# S01-INTERFACES.net
KiCad netlist of a schematic drawn in Altium Designer
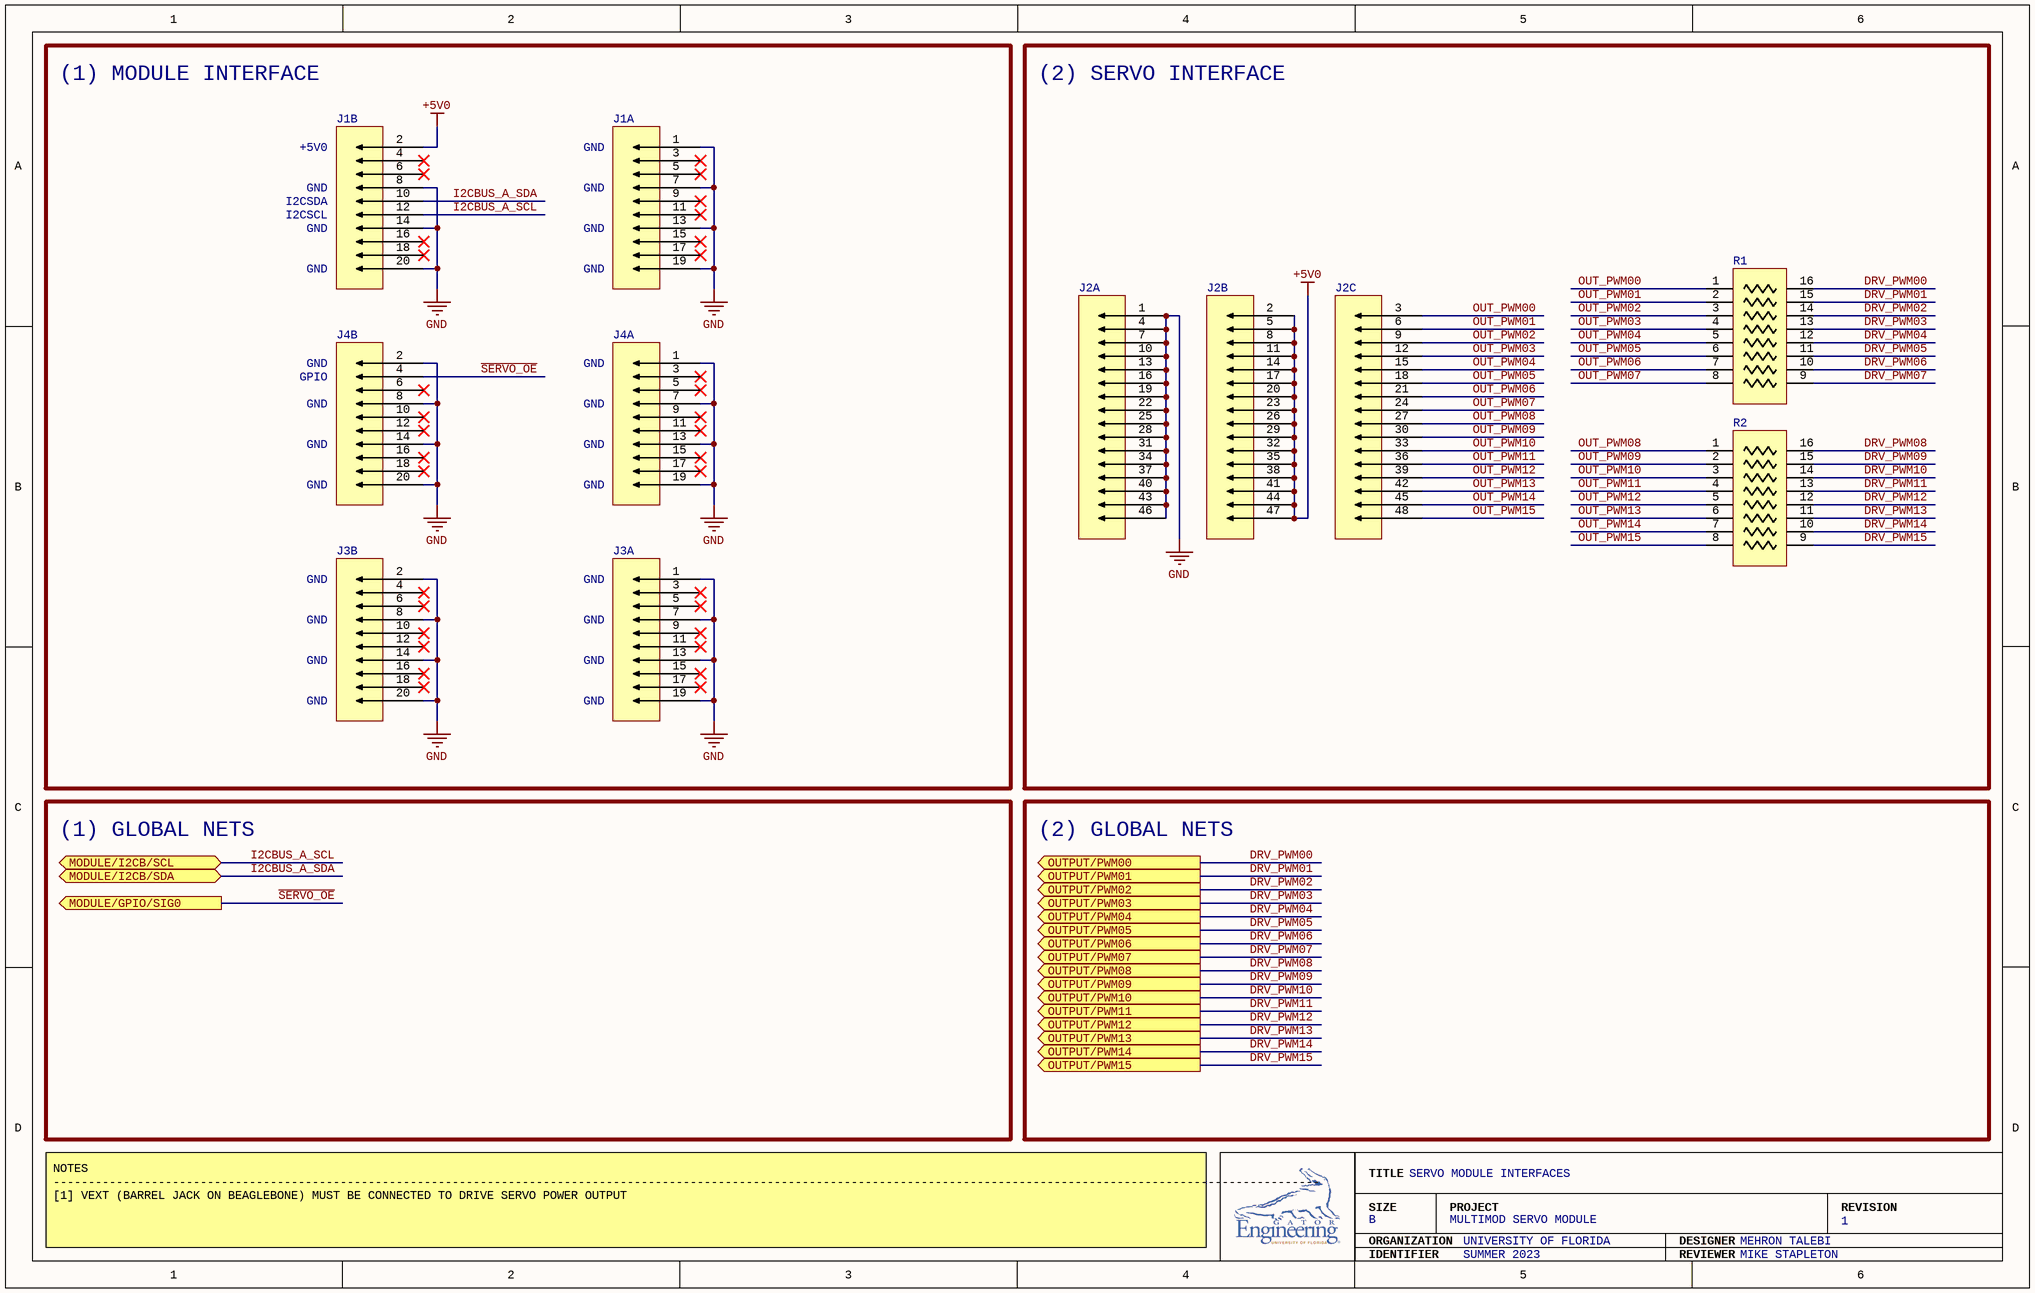
[diagram p0: S01-INTERFACES.SchDoc]

(export (version "E")
  (design (tool "Eeschema 10.0.6"))
  (components
    (comp (ref "J1")
      (value "NPTC102KFMS-RC")
      (footprint "NPTC102KFMS-RC")
      (description "CONN HDR 20POS 0.1 TIN SMD")
      (libsource (lib "Master") (part "NPTC102KFMS-RC"))
    )
    (comp (ref "J2")
      (value "TSW-116-07-L-T")
      (footprint "TSW-116-07-L-T")
      (description "CONN HEADER VERT 48POS 2.54MM")
      (libsource (lib "Master") (part "TSW-116-07-L-T"))
    )
    (comp (ref "J3")
      (value "NPTC102KFMS-RC")
      (footprint "NPTC102KFMS-RC")
      (description "CONN HDR 20POS 0.1 TIN SMD")
      (libsource (lib "Master") (part "NPTC102KFMS-RC"))
    )
    (comp (ref "J4")
      (value "NPTC102KFMS-RC")
      (footprint "NPTC102KFMS-RC")
      (description "CONN HDR 20POS 0.1 TIN SMD")
      (libsource (lib "Master") (part "NPTC102KFMS-RC"))
    )
    (comp (ref "R1")
      (value "EXB-2HV221JV")
      (footprint "EXB-2HV221JV")
      (description "RES ARRAY 8 RES 220 OHM 1506")
      (fields (field (name "TOLERANCE") "±5%"))
      (libsource (lib "Master") (part "EXB-2HV221JV"))
    )
    (comp (ref "R2")
      (value "EXB-2HV221JV")
      (footprint "EXB-2HV221JV")
      (description "RES ARRAY 8 RES 220 OHM 1506")
      (fields (field (name "TOLERANCE") "±5%"))
      (libsource (lib "Master") (part "EXB-2HV221JV"))
    )
  )
  (nets
    (net (code "1") (name "+5V0") (class "Default")
      (node (ref "J1") (pin "2") (pinfunction "2_2") (pintype "passive"))
      (node (ref "J2") (pin "11") (pinfunction "11_11") (pintype "passive"))
      (node (ref "J2") (pin "14") (pinfunction "14_14") (pintype "passive"))
      (node (ref "J2") (pin "17") (pinfunction "17_17") (pintype "passive"))
      (node (ref "J2") (pin "2") (pinfunction "2_2") (pintype "passive"))
      (node (ref "J2") (pin "20") (pinfunction "20_20") (pintype "passive"))
      (node (ref "J2") (pin "23") (pinfunction "23_23") (pintype "passive"))
      (node (ref "J2") (pin "26") (pinfunction "26_26") (pintype "passive"))
      (node (ref "J2") (pin "29") (pinfunction "29_29") (pintype "passive"))
      (node (ref "J2") (pin "32") (pinfunction "32_32") (pintype "passive"))
      (node (ref "J2") (pin "35") (pinfunction "35_35") (pintype "passive"))
      (node (ref "J2") (pin "38") (pinfunction "38_38") (pintype "passive"))
      (node (ref "J2") (pin "41") (pinfunction "41_41") (pintype "passive"))
      (node (ref "J2") (pin "44") (pinfunction "44_44") (pintype "passive"))
      (node (ref "J2") (pin "47") (pinfunction "47_47") (pintype "passive"))
      (node (ref "J2") (pin "5") (pinfunction "5_5") (pintype "passive"))
      (node (ref "J2") (pin "8") (pinfunction "8_8") (pintype "passive"))
    )
    (net (code "2") (name "/DRV_PWM00") (class "Default")
      (node (ref "R1") (pin "16") (pinfunction "16_16") (pintype "passive"))
    )
    (net (code "3") (name "/DRV_PWM01") (class "Default")
      (node (ref "R1") (pin "15") (pinfunction "15_15") (pintype "passive"))
    )
    (net (code "4") (name "/DRV_PWM02") (class "Default")
      (node (ref "R1") (pin "14") (pinfunction "14_14") (pintype "passive"))
    )
    (net (code "5") (name "/DRV_PWM03") (class "Default")
      (node (ref "R1") (pin "13") (pinfunction "13_13") (pintype "passive"))
    )
    (net (code "6") (name "/DRV_PWM04") (class "Default")
      (node (ref "R1") (pin "12") (pinfunction "12_12") (pintype "passive"))
    )
    (net (code "7") (name "/DRV_PWM05") (class "Default")
      (node (ref "R1") (pin "11") (pinfunction "11_11") (pintype "passive"))
    )
    (net (code "8") (name "/DRV_PWM06") (class "Default")
      (node (ref "R1") (pin "10") (pinfunction "10_10") (pintype "passive"))
    )
    (net (code "9") (name "/DRV_PWM07") (class "Default")
      (node (ref "R1") (pin "9") (pinfunction "9_9") (pintype "passive"))
    )
    (net (code "10") (name "/DRV_PWM08") (class "Default")
      (node (ref "R2") (pin "16") (pinfunction "16_16") (pintype "passive"))
    )
    (net (code "11") (name "/DRV_PWM09") (class "Default")
      (node (ref "R2") (pin "15") (pinfunction "15_15") (pintype "passive"))
    )
    (net (code "12") (name "/DRV_PWM10") (class "Default")
      (node (ref "R2") (pin "14") (pinfunction "14_14") (pintype "passive"))
    )
    (net (code "13") (name "/DRV_PWM11") (class "Default")
      (node (ref "R2") (pin "13") (pinfunction "13_13") (pintype "passive"))
    )
    (net (code "14") (name "/DRV_PWM12") (class "Default")
      (node (ref "R2") (pin "12") (pinfunction "12_12") (pintype "passive"))
    )
    (net (code "15") (name "/DRV_PWM13") (class "Default")
      (node (ref "R2") (pin "11") (pinfunction "11_11") (pintype "passive"))
    )
    (net (code "16") (name "/DRV_PWM14") (class "Default")
      (node (ref "R2") (pin "10") (pinfunction "10_10") (pintype "passive"))
    )
    (net (code "17") (name "/DRV_PWM15") (class "Default")
      (node (ref "R2") (pin "9") (pinfunction "9_9") (pintype "passive"))
    )
    (net (code "18") (name "/I2CBUS_A_SCL") (class "Default")
      (node (ref "J1") (pin "12") (pinfunction "12_12") (pintype "passive"))
    )
    (net (code "19") (name "/I2CBUS_A_SDA") (class "Default")
      (node (ref "J1") (pin "10") (pinfunction "10_10") (pintype "passive"))
    )
    (net (code "20") (name "/OUT_PWM00") (class "Default")
      (node (ref "J2") (pin "3") (pinfunction "3_3") (pintype "passive"))
      (node (ref "R1") (pin "1") (pinfunction "1_1") (pintype "passive"))
    )
    (net (code "21") (name "/OUT_PWM01") (class "Default")
      (node (ref "J2") (pin "6") (pinfunction "6_6") (pintype "passive"))
      (node (ref "R1") (pin "2") (pinfunction "2_2") (pintype "passive"))
    )
    (net (code "22") (name "/OUT_PWM02") (class "Default")
      (node (ref "J2") (pin "9") (pinfunction "9_9") (pintype "passive"))
      (node (ref "R1") (pin "3") (pinfunction "3_3") (pintype "passive"))
    )
    (net (code "23") (name "/OUT_PWM03") (class "Default")
      (node (ref "J2") (pin "12") (pinfunction "12_12") (pintype "passive"))
      (node (ref "R1") (pin "4") (pinfunction "4_4") (pintype "passive"))
    )
    (net (code "24") (name "/OUT_PWM04") (class "Default")
      (node (ref "J2") (pin "15") (pinfunction "15_15") (pintype "passive"))
      (node (ref "R1") (pin "5") (pinfunction "5_5") (pintype "passive"))
    )
    (net (code "25") (name "/OUT_PWM05") (class "Default")
      (node (ref "J2") (pin "18") (pinfunction "18_18") (pintype "passive"))
      (node (ref "R1") (pin "6") (pinfunction "6_6") (pintype "passive"))
    )
    (net (code "26") (name "/OUT_PWM06") (class "Default")
      (node (ref "J2") (pin "21") (pinfunction "21_21") (pintype "passive"))
      (node (ref "R1") (pin "7") (pinfunction "7_7") (pintype "passive"))
    )
    (net (code "27") (name "/OUT_PWM07") (class "Default")
      (node (ref "J2") (pin "24") (pinfunction "24_24") (pintype "passive"))
      (node (ref "R1") (pin "8") (pinfunction "8_8") (pintype "passive"))
    )
    (net (code "28") (name "/OUT_PWM08") (class "Default")
      (node (ref "J2") (pin "27") (pinfunction "27_27") (pintype "passive"))
      (node (ref "R2") (pin "1") (pinfunction "1_1") (pintype "passive"))
    )
    (net (code "29") (name "/OUT_PWM09") (class "Default")
      (node (ref "J2") (pin "30") (pinfunction "30_30") (pintype "passive"))
      (node (ref "R2") (pin "2") (pinfunction "2_2") (pintype "passive"))
    )
    (net (code "30") (name "/OUT_PWM10") (class "Default")
      (node (ref "J2") (pin "33") (pinfunction "33_33") (pintype "passive"))
      (node (ref "R2") (pin "3") (pinfunction "3_3") (pintype "passive"))
    )
    (net (code "31") (name "/OUT_PWM11") (class "Default")
      (node (ref "J2") (pin "36") (pinfunction "36_36") (pintype "passive"))
      (node (ref "R2") (pin "4") (pinfunction "4_4") (pintype "passive"))
    )
    (net (code "32") (name "/OUT_PWM12") (class "Default")
      (node (ref "J2") (pin "39") (pinfunction "39_39") (pintype "passive"))
      (node (ref "R2") (pin "5") (pinfunction "5_5") (pintype "passive"))
    )
    (net (code "33") (name "/OUT_PWM13") (class "Default")
      (node (ref "J2") (pin "42") (pinfunction "42_42") (pintype "passive"))
      (node (ref "R2") (pin "6") (pinfunction "6_6") (pintype "passive"))
    )
    (net (code "34") (name "/OUT_PWM14") (class "Default")
      (node (ref "J2") (pin "45") (pinfunction "45_45") (pintype "passive"))
      (node (ref "R2") (pin "7") (pinfunction "7_7") (pintype "passive"))
    )
    (net (code "35") (name "/OUT_PWM15") (class "Default")
      (node (ref "J2") (pin "48") (pinfunction "48_48") (pintype "passive"))
      (node (ref "R2") (pin "8") (pinfunction "8_8") (pintype "passive"))
    )
    (net (code "36") (name "/SERVO_OE") (class "Default")
      (node (ref "J4") (pin "4") (pinfunction "4_4") (pintype "passive"))
    )
    (net (code "37") (name "GND") (class "Default")
      (node (ref "J1") (pin "1") (pinfunction "1_1") (pintype "passive"))
      (node (ref "J1") (pin "13") (pinfunction "13_13") (pintype "passive"))
      (node (ref "J1") (pin "14") (pinfunction "14_14") (pintype "passive"))
      (node (ref "J1") (pin "19") (pinfunction "19_19") (pintype "passive"))
      (node (ref "J1") (pin "20") (pinfunction "20_20") (pintype "passive"))
      (node (ref "J1") (pin "7") (pinfunction "7_7") (pintype "passive"))
      (node (ref "J1") (pin "8") (pinfunction "8_8") (pintype "passive"))
      (node (ref "J2") (pin "1") (pinfunction "1_1") (pintype "passive"))
      (node (ref "J2") (pin "10") (pinfunction "10_10") (pintype "passive"))
      (node (ref "J2") (pin "13") (pinfunction "13_13") (pintype "passive"))
      (node (ref "J2") (pin "16") (pinfunction "16_16") (pintype "passive"))
      (node (ref "J2") (pin "19") (pinfunction "19_19") (pintype "passive"))
      (node (ref "J2") (pin "22") (pinfunction "22_22") (pintype "passive"))
      (node (ref "J2") (pin "25") (pinfunction "25_25") (pintype "passive"))
      (node (ref "J2") (pin "28") (pinfunction "28_28") (pintype "passive"))
      (node (ref "J2") (pin "31") (pinfunction "31_31") (pintype "passive"))
      (node (ref "J2") (pin "34") (pinfunction "34_34") (pintype "passive"))
      (node (ref "J2") (pin "37") (pinfunction "37_37") (pintype "passive"))
      (node (ref "J2") (pin "4") (pinfunction "4_4") (pintype "passive"))
      (node (ref "J2") (pin "40") (pinfunction "40_40") (pintype "passive"))
      (node (ref "J2") (pin "43") (pinfunction "43_43") (pintype "passive"))
      (node (ref "J2") (pin "46") (pinfunction "46_46") (pintype "passive"))
      (node (ref "J2") (pin "7") (pinfunction "7_7") (pintype "passive"))
      (node (ref "J3") (pin "1") (pinfunction "1_1") (pintype "passive"))
      (node (ref "J3") (pin "13") (pinfunction "13_13") (pintype "passive"))
      (node (ref "J3") (pin "14") (pinfunction "14_14") (pintype "passive"))
      (node (ref "J3") (pin "19") (pinfunction "19_19") (pintype "passive"))
      (node (ref "J3") (pin "2") (pinfunction "2_2") (pintype "passive"))
      (node (ref "J3") (pin "20") (pinfunction "20_20") (pintype "passive"))
      (node (ref "J3") (pin "7") (pinfunction "7_7") (pintype "passive"))
      (node (ref "J3") (pin "8") (pinfunction "8_8") (pintype "passive"))
      (node (ref "J4") (pin "1") (pinfunction "1_1") (pintype "passive"))
      (node (ref "J4") (pin "13") (pinfunction "13_13") (pintype "passive"))
      (node (ref "J4") (pin "14") (pinfunction "14_14") (pintype "passive"))
      (node (ref "J4") (pin "19") (pinfunction "19_19") (pintype "passive"))
      (node (ref "J4") (pin "2") (pinfunction "2_2") (pintype "passive"))
      (node (ref "J4") (pin "20") (pinfunction "20_20") (pintype "passive"))
      (node (ref "J4") (pin "7") (pinfunction "7_7") (pintype "passive"))
      (node (ref "J4") (pin "8") (pinfunction "8_8") (pintype "passive"))
    )
    (net (code "38") (name "unconnected-(J1-Pad3)") (class "Default")
      (node (ref "J1") (pin "3") (pinfunction "3_3") (pintype "passive+no_connect"))
    )
    (net (code "39") (name "unconnected-(J1-Pad4)") (class "Default")
      (node (ref "J1") (pin "4") (pinfunction "4_4") (pintype "passive+no_connect"))
    )
    (net (code "40") (name "unconnected-(J1-Pad5)") (class "Default")
      (node (ref "J1") (pin "5") (pinfunction "5_5") (pintype "passive+no_connect"))
    )
    (net (code "41") (name "unconnected-(J1-Pad6)") (class "Default")
      (node (ref "J1") (pin "6") (pinfunction "6_6") (pintype "passive+no_connect"))
    )
    (net (code "42") (name "unconnected-(J1-Pad9)") (class "Default")
      (node (ref "J1") (pin "9") (pinfunction "9_9") (pintype "passive+no_connect"))
    )
    (net (code "43") (name "unconnected-(J1-Pad11)") (class "Default")
      (node (ref "J1") (pin "11") (pinfunction "11_11") (pintype "passive+no_connect"))
    )
    (net (code "44") (name "unconnected-(J1-Pad15)") (class "Default")
      (node (ref "J1") (pin "15") (pinfunction "15_15") (pintype "passive+no_connect"))
    )
    (net (code "45") (name "unconnected-(J1-Pad16)") (class "Default")
      (node (ref "J1") (pin "16") (pinfunction "16_16") (pintype "passive+no_connect"))
    )
    (net (code "46") (name "unconnected-(J1-Pad17)") (class "Default")
      (node (ref "J1") (pin "17") (pinfunction "17_17") (pintype "passive+no_connect"))
    )
    (net (code "47") (name "unconnected-(J1-Pad18)") (class "Default")
      (node (ref "J1") (pin "18") (pinfunction "18_18") (pintype "passive+no_connect"))
    )
    (net (code "48") (name "unconnected-(J3-Pad3)") (class "Default")
      (node (ref "J3") (pin "3") (pinfunction "3_3") (pintype "passive+no_connect"))
    )
    (net (code "49") (name "unconnected-(J3-Pad4)") (class "Default")
      (node (ref "J3") (pin "4") (pinfunction "4_4") (pintype "passive+no_connect"))
    )
    (net (code "50") (name "unconnected-(J3-Pad5)") (class "Default")
      (node (ref "J3") (pin "5") (pinfunction "5_5") (pintype "passive+no_connect"))
    )
    (net (code "51") (name "unconnected-(J3-Pad6)") (class "Default")
      (node (ref "J3") (pin "6") (pinfunction "6_6") (pintype "passive+no_connect"))
    )
    (net (code "52") (name "unconnected-(J3-Pad9)") (class "Default")
      (node (ref "J3") (pin "9") (pinfunction "9_9") (pintype "passive+no_connect"))
    )
    (net (code "53") (name "unconnected-(J3-Pad10)") (class "Default")
      (node (ref "J3") (pin "10") (pinfunction "10_10") (pintype "passive+no_connect"))
    )
    (net (code "54") (name "unconnected-(J3-Pad11)") (class "Default")
      (node (ref "J3") (pin "11") (pinfunction "11_11") (pintype "passive+no_connect"))
    )
    (net (code "55") (name "unconnected-(J3-Pad12)") (class "Default")
      (node (ref "J3") (pin "12") (pinfunction "12_12") (pintype "passive+no_connect"))
    )
    (net (code "56") (name "unconnected-(J3-Pad15)") (class "Default")
      (node (ref "J3") (pin "15") (pinfunction "15_15") (pintype "passive+no_connect"))
    )
    (net (code "57") (name "unconnected-(J3-Pad16)") (class "Default")
      (node (ref "J3") (pin "16") (pinfunction "16_16") (pintype "passive+no_connect"))
    )
    (net (code "58") (name "unconnected-(J3-Pad17)") (class "Default")
      (node (ref "J3") (pin "17") (pinfunction "17_17") (pintype "passive+no_connect"))
    )
    (net (code "59") (name "unconnected-(J3-Pad18)") (class "Default")
      (node (ref "J3") (pin "18") (pinfunction "18_18") (pintype "passive+no_connect"))
    )
    (net (code "60") (name "unconnected-(J4-Pad3)") (class "Default")
      (node (ref "J4") (pin "3") (pinfunction "3_3") (pintype "passive+no_connect"))
    )
    (net (code "61") (name "unconnected-(J4-Pad5)") (class "Default")
      (node (ref "J4") (pin "5") (pinfunction "5_5") (pintype "passive+no_connect"))
    )
    (net (code "62") (name "unconnected-(J4-Pad6)") (class "Default")
      (node (ref "J4") (pin "6") (pinfunction "6_6") (pintype "passive+no_connect"))
    )
    (net (code "63") (name "unconnected-(J4-Pad9)") (class "Default")
      (node (ref "J4") (pin "9") (pinfunction "9_9") (pintype "passive+no_connect"))
    )
    (net (code "64") (name "unconnected-(J4-Pad10)") (class "Default")
      (node (ref "J4") (pin "10") (pinfunction "10_10") (pintype "passive+no_connect"))
    )
    (net (code "65") (name "unconnected-(J4-Pad11)") (class "Default")
      (node (ref "J4") (pin "11") (pinfunction "11_11") (pintype "passive+no_connect"))
    )
    (net (code "66") (name "unconnected-(J4-Pad12)") (class "Default")
      (node (ref "J4") (pin "12") (pinfunction "12_12") (pintype "passive+no_connect"))
    )
    (net (code "67") (name "unconnected-(J4-Pad15)") (class "Default")
      (node (ref "J4") (pin "15") (pinfunction "15_15") (pintype "passive+no_connect"))
    )
    (net (code "68") (name "unconnected-(J4-Pad16)") (class "Default")
      (node (ref "J4") (pin "16") (pinfunction "16_16") (pintype "passive+no_connect"))
    )
    (net (code "69") (name "unconnected-(J4-Pad17)") (class "Default")
      (node (ref "J4") (pin "17") (pinfunction "17_17") (pintype "passive+no_connect"))
    )
    (net (code "70") (name "unconnected-(J4-Pad18)") (class "Default")
      (node (ref "J4") (pin "18") (pinfunction "18_18") (pintype "passive+no_connect"))
    )
  )
)
